# cyboard.net
KiCad netlist of a schematic drawn in EAGLE
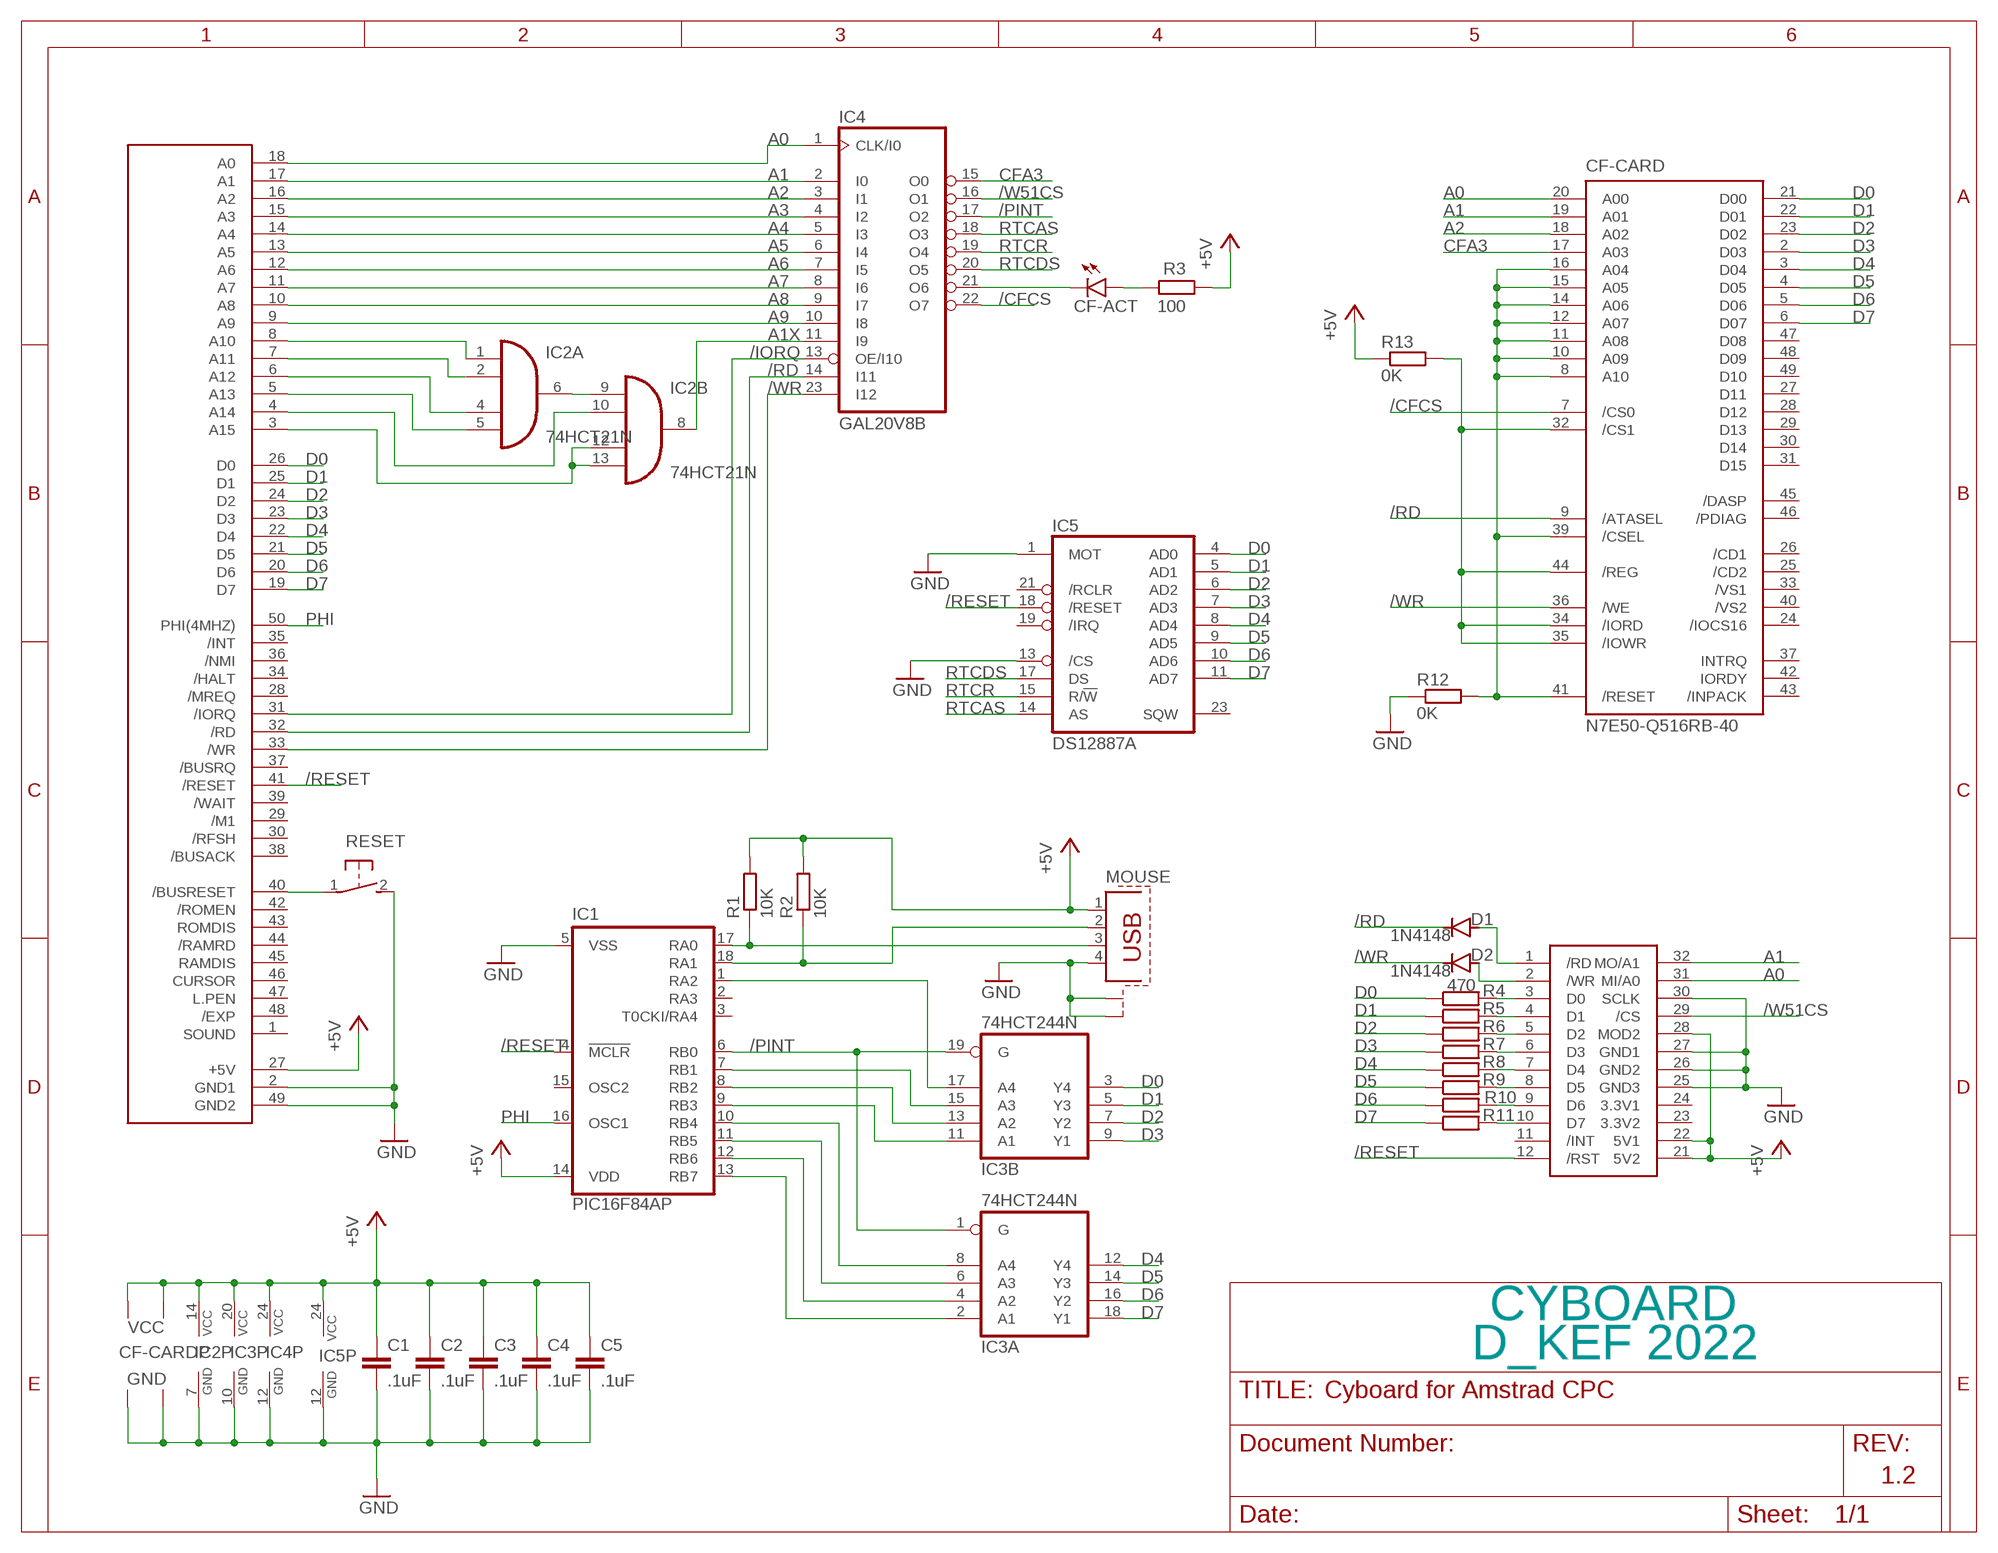
[diagram p0: schematic, sheet 1]

(export (version "E")
  (design (tool "Eeschema 10.0.6"))
  (components
    (comp (ref "C1")
      (value ".1uF")
      (footprint "eagle-import:C025-025X050")
      (libsource (lib "eagle-import") (part "C-EU025-025X050"))
    )
    (comp (ref "C2")
      (value ".1uF")
      (footprint "eagle-import:C025-025X050")
      (libsource (lib "eagle-import") (part "C-EU025-025X050"))
    )
    (comp (ref "C3")
      (value ".1uF")
      (footprint "eagle-import:C025-025X050")
      (libsource (lib "eagle-import") (part "C-EU025-025X050"))
    )
    (comp (ref "C4")
      (value ".1uF")
      (footprint "eagle-import:C025-025X050")
      (libsource (lib "eagle-import") (part "C-EU025-025X050"))
    )
    (comp (ref "C5")
      (value ".1uF")
      (footprint "eagle-import:C025-025X050")
      (libsource (lib "eagle-import") (part "C-EU025-025X050"))
    )
    (comp (ref "CF-ACT")
      (value "CF ACT")
      (footprint "eagle-import:LED3MM")
      (libsource (lib "eagle-import") (part "LED3MM"))
    )
    (comp (ref "CF-CARD")
      (value "N7E50-Q516RB-40")
      (footprint "eagle-import:3M-N7E50")
      (libsource (lib "eagle-import") (part "CF-CARD-HEADERHYBRID-1"))
    )
    (comp (ref "CON1")
      (value "CPCBUS")
      (footprint "eagle-import:2X25")
      (libsource (lib "eagle-import") (part "AMSTRAD_CPC_BUSP"))
    )
    (comp (ref "D1")
      (value "1N4148")
      (footprint "eagle-import:DO35-7")
      (libsource (lib "eagle-import") (part "1N4148DO35-7"))
    )
    (comp (ref "D2")
      (value "1N4148")
      (footprint "eagle-import:DO35-7")
      (libsource (lib "eagle-import") (part "1N4148DO35-7"))
    )
    (comp (ref "IC1")
      (value "PIC16F84AP")
      (footprint "eagle-import:DIL18")
      (fields (field (name "MF") "MICROCHIP") (field (name "MPN") "PIC16F84A-04I/P"))
      (libsource (lib "eagle-import") (part "PIC16F8P4A"))
    )
    (comp (ref "IC2")
      (value "74HCT21N")
      (footprint "eagle-import:DIL14")
      (libsource (lib "eagle-import") (part "7421NHC"))
    )
    (comp (ref "IC3")
      (value "74HCT244N")
      (footprint "eagle-import:DIL20")
      (libsource (lib "eagle-import") (part "74244NHCT"))
    )
    (comp (ref "IC4")
      (value "GAL20V8B")
      (footprint "eagle-import:DIL24-3")
      (fields (field (name "MF") "FARNELL") (field (name "MPN") "GAL20V8B-25QP"))
      (libsource (lib "eagle-import") (part "20V8"))
    )
    (comp (ref "IC5")
      (value "DS12887A")
      (footprint "eagle-import:DIL24")
      (libsource (lib "eagle-import") (part "DS12887"))
    )
    (comp (ref "MOUSE")
      (value "PN87520-S")
      (footprint "eagle-import:PN87520-S")
      (libsource (lib "eagle-import") (part "PN87520-S"))
    )
    (comp (ref "R1")
      (value "10K")
      (footprint "eagle-import:0204_7")
      (libsource (lib "eagle-import") (part "R-EU_0204/7"))
    )
    (comp (ref "R2")
      (value "10K")
      (footprint "eagle-import:0204_7")
      (libsource (lib "eagle-import") (part "R-EU_0204/7"))
    )
    (comp (ref "R3")
      (value "100")
      (footprint "eagle-import:0204_7")
      (libsource (lib "eagle-import") (part "R-EU_0204/7"))
    )
    (comp (ref "R4")
      (value "470")
      (footprint "eagle-import:0204_7")
      (libsource (lib "eagle-import") (part "R-EU_0204/7"))
    )
    (comp (ref "R5")
      (value "470")
      (footprint "eagle-import:0204_7")
      (libsource (lib "eagle-import") (part "R-EU_0204/7"))
    )
    (comp (ref "R6")
      (value "470")
      (footprint "eagle-import:0204_7")
      (libsource (lib "eagle-import") (part "R-EU_0204/7"))
    )
    (comp (ref "R7")
      (value "470")
      (footprint "eagle-import:0204_7")
      (libsource (lib "eagle-import") (part "R-EU_0204/7"))
    )
    (comp (ref "R8")
      (value "470")
      (footprint "eagle-import:0204_7")
      (libsource (lib "eagle-import") (part "R-EU_0204/7"))
    )
    (comp (ref "R9")
      (value "470")
      (footprint "eagle-import:0204_7")
      (libsource (lib "eagle-import") (part "R-EU_0204/7"))
    )
    (comp (ref "R10")
      (value "470")
      (footprint "eagle-import:0204_7")
      (libsource (lib "eagle-import") (part "R-EU_0204/7"))
    )
    (comp (ref "R11")
      (value "470")
      (footprint "eagle-import:0204_7")
      (libsource (lib "eagle-import") (part "R-EU_0204/7"))
    )
    (comp (ref "R12")
      (value "0K")
      (footprint "eagle-import:0204_7")
      (libsource (lib "eagle-import") (part "R-EU_0204/7"))
    )
    (comp (ref "R13")
      (value "0K")
      (footprint "eagle-import:0204_7")
      (libsource (lib "eagle-import") (part "R-EU_0204/7"))
    )
    (comp (ref "RESET")
      (value "Reset")
      (footprint "eagle-import:B3F-31XX")
      (fields (field (name "MPN") "B3F-3100"))
      (libsource (lib "eagle-import") (part "31-XX"))
    )
    (comp (ref "W5100S-MODULE")
      (value "W5100S-NETWORK-MODULE")
      (footprint "eagle-import:W5100S-NETWORK-MODULE")
      (libsource (lib "eagle-import") (part "W5100S-NETWORK-MODULE"))
    )
  )
  (nets
    (net (code "1") (name "+5V") (class "Default")
      (node (ref "C1") (pin "1") (pinfunction "1_1") (pintype "passive"))
      (node (ref "C2") (pin "1") (pinfunction "1_1") (pintype "passive"))
      (node (ref "C3") (pin "1") (pinfunction "1_1") (pintype "passive"))
      (node (ref "C4") (pin "1") (pinfunction "1_1") (pintype "passive"))
      (node (ref "C5") (pin "1") (pinfunction "1_1") (pintype "passive"))
      (node (ref "CF-CARD") (pin "13") (pinfunction "VCC2_13") (pintype "power_in"))
      (node (ref "CF-CARD") (pin "38") (pinfunction "VCC1_38") (pintype "power_in"))
      (node (ref "CON1") (pin "27") (pinfunction "+5V_27") (pintype "bidirectional"))
      (node (ref "IC1") (pin "14") (pinfunction "VDD_14") (pintype "power_in"))
      (node (ref "IC2") (pin "14") (pinfunction "VCC_14") (pintype "power_in"))
      (node (ref "IC3") (pin "20") (pinfunction "VCC_20") (pintype "power_in"))
      (node (ref "IC4") (pin "24") (pinfunction "VCC_24") (pintype "power_in"))
      (node (ref "IC5") (pin "24") (pinfunction "VCC_24") (pintype "power_in"))
      (node (ref "MOUSE") (pin "1") (pinfunction "1_1") (pintype "passive"))
      (node (ref "R1") (pin "2") (pinfunction "2_2") (pintype "passive"))
      (node (ref "R13") (pin "1") (pinfunction "1_1") (pintype "passive"))
      (node (ref "R2") (pin "2") (pinfunction "2_2") (pintype "passive"))
      (node (ref "R3") (pin "1") (pinfunction "1_1") (pintype "passive"))
      (node (ref "W5100S-MODULE") (pin "21") (pinfunction "5V2_21") (pintype "power_in"))
      (node (ref "W5100S-MODULE") (pin "22") (pinfunction "5V1_22") (pintype "power_in"))
      (node (ref "W5100S-MODULE") (pin "28") (pinfunction "MOD2_28") (pintype "passive"))
    )
    (net (code "2") (name "/3.3V1") (class "Default")
      (node (ref "W5100S-MODULE") (pin "24") (pinfunction "3.3V1_24") (pintype "power_in"))
    )
    (net (code "3") (name "/3.3V2") (class "Default")
      (node (ref "W5100S-MODULE") (pin "23") (pinfunction "3.3V2_23") (pintype "power_in"))
    )
    (net (code "4") (name "/A0") (class "Default")
      (node (ref "CF-CARD") (pin "20") (pinfunction "A00_20") (pintype "input"))
      (node (ref "CON1") (pin "18") (pinfunction "A0_18") (pintype "bidirectional"))
      (node (ref "IC4") (pin "1") (pinfunction "CLK/I0_1") (pintype "input"))
      (node (ref "W5100S-MODULE") (pin "31") (pinfunction "MI/A0_31") (pintype "input"))
    )
    (net (code "5") (name "/A1") (class "Default")
      (node (ref "CF-CARD") (pin "19") (pinfunction "A01_19") (pintype "input"))
      (node (ref "CON1") (pin "17") (pinfunction "A1_17") (pintype "bidirectional"))
      (node (ref "IC4") (pin "2") (pinfunction "I0_2") (pintype "input"))
      (node (ref "W5100S-MODULE") (pin "32") (pinfunction "MO/A1_32") (pintype "bidirectional"))
    )
    (net (code "6") (name "/A1X") (class "Default")
      (node (ref "IC2") (pin "8") (pinfunction "O_8") (pintype "output"))
      (node (ref "IC4") (pin "11") (pinfunction "I9_11") (pintype "input"))
    )
    (net (code "7") (name "/A2") (class "Default")
      (node (ref "CF-CARD") (pin "18") (pinfunction "A02_18") (pintype "input"))
      (node (ref "CON1") (pin "16") (pinfunction "A2_16") (pintype "bidirectional"))
      (node (ref "IC4") (pin "3") (pinfunction "I1_3") (pintype "input"))
    )
    (net (code "8") (name "/A3") (class "Default")
      (node (ref "CON1") (pin "15") (pinfunction "A3_15") (pintype "bidirectional"))
      (node (ref "IC4") (pin "4") (pinfunction "I2_4") (pintype "input"))
    )
    (net (code "9") (name "/A4") (class "Default")
      (node (ref "CON1") (pin "14") (pinfunction "A4_14") (pintype "bidirectional"))
      (node (ref "IC4") (pin "5") (pinfunction "I3_5") (pintype "input"))
    )
    (net (code "10") (name "/A5") (class "Default")
      (node (ref "CON1") (pin "13") (pinfunction "A5_13") (pintype "bidirectional"))
      (node (ref "IC4") (pin "6") (pinfunction "I4_6") (pintype "input"))
    )
    (net (code "11") (name "/A6") (class "Default")
      (node (ref "CON1") (pin "12") (pinfunction "A6_12") (pintype "bidirectional"))
      (node (ref "IC4") (pin "7") (pinfunction "I5_7") (pintype "input"))
    )
    (net (code "12") (name "/A7") (class "Default")
      (node (ref "CON1") (pin "11") (pinfunction "A7_11") (pintype "bidirectional"))
      (node (ref "IC4") (pin "8") (pinfunction "I6_8") (pintype "input"))
    )
    (net (code "13") (name "/A8") (class "Default")
      (node (ref "CON1") (pin "10") (pinfunction "A8_10") (pintype "bidirectional"))
      (node (ref "IC4") (pin "9") (pinfunction "I7_9") (pintype "input"))
    )
    (net (code "14") (name "/A9") (class "Default")
      (node (ref "CON1") (pin "9") (pinfunction "A9_9") (pintype "bidirectional"))
      (node (ref "IC4") (pin "10") (pinfunction "I8_10") (pintype "input"))
    )
    (net (code "15") (name "/CFA3") (class "Default")
      (node (ref "CF-CARD") (pin "17") (pinfunction "A03_17") (pintype "input"))
      (node (ref "IC4") (pin "15") (pinfunction "O0_15") (pintype "bidirectional"))
    )
    (net (code "16") (name "/D0") (class "Default")
      (node (ref "CF-CARD") (pin "21") (pinfunction "D00_21") (pintype "bidirectional"))
      (node (ref "CON1") (pin "26") (pinfunction "D0_26") (pintype "bidirectional"))
      (node (ref "IC3") (pin "3") (pinfunction "Y4_3") (pintype "tri_state"))
      (node (ref "IC5") (pin "4") (pinfunction "AD0_4") (pintype "bidirectional"))
      (node (ref "R4") (pin "1") (pinfunction "1_1") (pintype "passive"))
    )
    (net (code "17") (name "/D1") (class "Default")
      (node (ref "CF-CARD") (pin "22") (pinfunction "D01_22") (pintype "bidirectional"))
      (node (ref "CON1") (pin "25") (pinfunction "D1_25") (pintype "bidirectional"))
      (node (ref "IC3") (pin "5") (pinfunction "Y3_5") (pintype "tri_state"))
      (node (ref "IC5") (pin "5") (pinfunction "AD1_5") (pintype "bidirectional"))
      (node (ref "R5") (pin "1") (pinfunction "1_1") (pintype "passive"))
    )
    (net (code "18") (name "/D2") (class "Default")
      (node (ref "CF-CARD") (pin "23") (pinfunction "D02_23") (pintype "bidirectional"))
      (node (ref "CON1") (pin "24") (pinfunction "D2_24") (pintype "bidirectional"))
      (node (ref "IC3") (pin "7") (pinfunction "Y2_7") (pintype "tri_state"))
      (node (ref "IC5") (pin "6") (pinfunction "AD2_6") (pintype "bidirectional"))
      (node (ref "R6") (pin "1") (pinfunction "1_1") (pintype "passive"))
    )
    (net (code "19") (name "/D3") (class "Default")
      (node (ref "CF-CARD") (pin "2") (pinfunction "D03_2") (pintype "bidirectional"))
      (node (ref "CON1") (pin "23") (pinfunction "D3_23") (pintype "bidirectional"))
      (node (ref "IC3") (pin "9") (pinfunction "Y1_9") (pintype "tri_state"))
      (node (ref "IC5") (pin "7") (pinfunction "AD3_7") (pintype "bidirectional"))
      (node (ref "R7") (pin "1") (pinfunction "1_1") (pintype "passive"))
    )
    (net (code "20") (name "/D4") (class "Default")
      (node (ref "CF-CARD") (pin "3") (pinfunction "D04_3") (pintype "bidirectional"))
      (node (ref "CON1") (pin "22") (pinfunction "D4_22") (pintype "bidirectional"))
      (node (ref "IC3") (pin "12") (pinfunction "Y4_12") (pintype "tri_state"))
      (node (ref "IC5") (pin "8") (pinfunction "AD4_8") (pintype "bidirectional"))
      (node (ref "R8") (pin "1") (pinfunction "1_1") (pintype "passive"))
    )
    (net (code "21") (name "/D5") (class "Default")
      (node (ref "CF-CARD") (pin "4") (pinfunction "D05_4") (pintype "bidirectional"))
      (node (ref "CON1") (pin "21") (pinfunction "D5_21") (pintype "bidirectional"))
      (node (ref "IC3") (pin "14") (pinfunction "Y3_14") (pintype "tri_state"))
      (node (ref "IC5") (pin "9") (pinfunction "AD5_9") (pintype "bidirectional"))
      (node (ref "R9") (pin "1") (pinfunction "1_1") (pintype "passive"))
    )
    (net (code "22") (name "/D6") (class "Default")
      (node (ref "CF-CARD") (pin "5") (pinfunction "D06_5") (pintype "bidirectional"))
      (node (ref "CON1") (pin "20") (pinfunction "D6_20") (pintype "bidirectional"))
      (node (ref "IC3") (pin "16") (pinfunction "Y2_16") (pintype "tri_state"))
      (node (ref "IC5") (pin "10") (pinfunction "AD6_10") (pintype "bidirectional"))
      (node (ref "R10") (pin "1") (pinfunction "1_1") (pintype "passive"))
    )
    (net (code "23") (name "/D7") (class "Default")
      (node (ref "CF-CARD") (pin "6") (pinfunction "D07_6") (pintype "bidirectional"))
      (node (ref "CON1") (pin "19") (pinfunction "D7_19") (pintype "bidirectional"))
      (node (ref "IC3") (pin "18") (pinfunction "Y1_18") (pintype "tri_state"))
      (node (ref "IC5") (pin "11") (pinfunction "AD7_11") (pintype "bidirectional"))
      (node (ref "R11") (pin "1") (pinfunction "1_1") (pintype "passive"))
    )
    (net (code "24") (name "/PHI") (class "Default")
      (node (ref "CON1") (pin "50") (pinfunction "PHI(4MHZ)_50") (pintype "bidirectional"))
      (node (ref "IC1") (pin "16") (pinfunction "OSC1_16") (pintype "input"))
    )
    (net (code "25") (name "/RTCAS") (class "Default")
      (node (ref "IC4") (pin "18") (pinfunction "O3_18") (pintype "bidirectional"))
      (node (ref "IC5") (pin "14") (pinfunction "AS_14") (pintype "input"))
    )
    (net (code "26") (name "/RTCDS") (class "Default")
      (node (ref "IC4") (pin "20") (pinfunction "O5_20") (pintype "bidirectional"))
      (node (ref "IC5") (pin "17") (pinfunction "DS_17") (pintype "input"))
    )
    (net (code "27") (name "/RTCR") (class "Default")
      (node (ref "IC4") (pin "19") (pinfunction "O4_19") (pintype "bidirectional"))
      (node (ref "IC5") (pin "15") (pinfunction "R/~{W}_15") (pintype "input"))
    )
    (net (code "28") (name "/{slash}CFCS") (class "Default")
      (node (ref "CF-CARD") (pin "7") (pinfunction "/CS0_7") (pintype "input"))
      (node (ref "IC4") (pin "22") (pinfunction "O7_22") (pintype "bidirectional"))
    )
    (net (code "29") (name "/{slash}IORQ") (class "Default")
      (node (ref "CON1") (pin "31") (pinfunction "/IORQ_31") (pintype "bidirectional"))
      (node (ref "IC4") (pin "13") (pinfunction "OE/I10_13") (pintype "input"))
    )
    (net (code "30") (name "/{slash}PINT") (class "Default")
      (node (ref "IC1") (pin "6") (pinfunction "RB0_6") (pintype "bidirectional"))
      (node (ref "IC3") (pin "1") (pinfunction "G_1") (pintype "input"))
      (node (ref "IC3") (pin "19") (pinfunction "G_19") (pintype "input"))
      (node (ref "IC4") (pin "17") (pinfunction "O2_17") (pintype "bidirectional"))
    )
    (net (code "31") (name "/{slash}RD") (class "Default")
      (node (ref "CF-CARD") (pin "9") (pinfunction "/ATASEL_9") (pintype "input"))
      (node (ref "CON1") (pin "32") (pinfunction "/RD_32") (pintype "bidirectional"))
      (node (ref "D1") (pin "C") (pinfunction "C_C") (pintype "passive"))
      (node (ref "IC4") (pin "14") (pinfunction "I11_14") (pintype "input"))
    )
    (net (code "32") (name "/{slash}RESET") (class "Default")
      (node (ref "CON1") (pin "41") (pinfunction "/RESET_41") (pintype "bidirectional"))
      (node (ref "IC1") (pin "4") (pinfunction "~{MCLR}_4") (pintype "input"))
      (node (ref "IC5") (pin "18") (pinfunction "/RESET_18") (pintype "input"))
      (node (ref "W5100S-MODULE") (pin "12") (pinfunction "/RST_12") (pintype "input"))
    )
    (net (code "33") (name "/{slash}W51CS") (class "Default")
      (node (ref "IC4") (pin "16") (pinfunction "O1_16") (pintype "bidirectional"))
      (node (ref "W5100S-MODULE") (pin "29") (pinfunction "/CS_29") (pintype "input"))
    )
    (net (code "34") (name "/{slash}WR") (class "Default")
      (node (ref "CF-CARD") (pin "36") (pinfunction "/WE_36") (pintype "input"))
      (node (ref "CON1") (pin "33") (pinfunction "/WR_33") (pintype "bidirectional"))
      (node (ref "D2") (pin "C") (pinfunction "C_C") (pintype "passive"))
      (node (ref "IC4") (pin "23") (pinfunction "I12_23") (pintype "input"))
    )
    (net (code "35") (name "GND") (class "Default")
      (node (ref "C1") (pin "2") (pinfunction "2_2") (pintype "passive"))
      (node (ref "C2") (pin "2") (pinfunction "2_2") (pintype "passive"))
      (node (ref "C3") (pin "2") (pinfunction "2_2") (pintype "passive"))
      (node (ref "C4") (pin "2") (pinfunction "2_2") (pintype "passive"))
      (node (ref "C5") (pin "2") (pinfunction "2_2") (pintype "passive"))
      (node (ref "CF-CARD") (pin "1") (pinfunction "GND1_1") (pintype "power_in"))
      (node (ref "CF-CARD") (pin "50") (pinfunction "GND2_50") (pintype "power_in"))
      (node (ref "CON1") (pin "2") (pinfunction "GND1_2") (pintype "bidirectional"))
      (node (ref "CON1") (pin "49") (pinfunction "GND2_49") (pintype "bidirectional"))
      (node (ref "IC1") (pin "5") (pinfunction "VSS_5") (pintype "power_in"))
      (node (ref "IC2") (pin "7") (pinfunction "GND_7") (pintype "power_in"))
      (node (ref "IC3") (pin "10") (pinfunction "GND_10") (pintype "power_in"))
      (node (ref "IC4") (pin "12") (pinfunction "GND_12") (pintype "power_in"))
      (node (ref "IC5") (pin "1") (pinfunction "MOT_1") (pintype "input"))
      (node (ref "IC5") (pin "12") (pinfunction "GND_12") (pintype "power_in"))
      (node (ref "IC5") (pin "13") (pinfunction "/CS_13") (pintype "input"))
      (node (ref "MOUSE") (pin "4") (pinfunction "4_4") (pintype "passive"))
      (node (ref "MOUSE") (pin "S1") (pinfunction "S1_S1") (pintype "passive"))
      (node (ref "MOUSE") (pin "S2") (pinfunction "S2_S2") (pintype "passive"))
      (node (ref "R12") (pin "1") (pinfunction "1_1") (pintype "passive"))
      (node (ref "RESET") (pin "2") (pinfunction "S_2") (pintype "passive"))
      (node (ref "W5100S-MODULE") (pin "25") (pinfunction "GND3_25") (pintype "power_in"))
      (node (ref "W5100S-MODULE") (pin "26") (pinfunction "GND2_26") (pintype "power_in"))
      (node (ref "W5100S-MODULE") (pin "27") (pinfunction "GND1_27") (pintype "power_in"))
      (node (ref "W5100S-MODULE") (pin "30") (pinfunction "SCLK_30") (pintype "output"))
    )
    (net (code "36") (name "Net-(CF-ACT-C)") (class "Default")
      (node (ref "CF-ACT") (pin "K") (pinfunction "C_K") (pintype "passive"))
      (node (ref "IC4") (pin "21") (pinfunction "O6_21") (pintype "bidirectional"))
    )
    (net (code "37") (name "Net-(CF-ACT-PadA)") (class "Default")
      (node (ref "CF-ACT") (pin "A") (pinfunction "A_A") (pintype "passive"))
      (node (ref "R3") (pin "2") (pinfunction "2_2") (pintype "passive"))
    )
    (net (code "38") (name "Net-(CF-CARDA-A04)") (class "Default")
      (node (ref "CF-CARD") (pin "10") (pinfunction "A09_10") (pintype "input"))
      (node (ref "CF-CARD") (pin "11") (pinfunction "A08_11") (pintype "input"))
      (node (ref "CF-CARD") (pin "12") (pinfunction "A07_12") (pintype "input"))
      (node (ref "CF-CARD") (pin "14") (pinfunction "A06_14") (pintype "input"))
      (node (ref "CF-CARD") (pin "15") (pinfunction "A05_15") (pintype "input"))
      (node (ref "CF-CARD") (pin "16") (pinfunction "A04_16") (pintype "input"))
      (node (ref "CF-CARD") (pin "39") (pinfunction "/CSEL_39") (pintype "input"))
      (node (ref "CF-CARD") (pin "41") (pinfunction "/RESET_41") (pintype "input"))
      (node (ref "CF-CARD") (pin "8") (pinfunction "A10_8") (pintype "input"))
      (node (ref "R12") (pin "2") (pinfunction "2_2") (pintype "passive"))
    )
    (net (code "39") (name "Net-(CF-CARDA-{slash}CS1)") (class "Default")
      (node (ref "CF-CARD") (pin "32") (pinfunction "/CS1_32") (pintype "input"))
      (node (ref "CF-CARD") (pin "34") (pinfunction "/IORD_34") (pintype "input"))
      (node (ref "CF-CARD") (pin "35") (pinfunction "/IOWR_35") (pintype "input"))
      (node (ref "CF-CARD") (pin "44") (pinfunction "/REG_44") (pintype "input"))
      (node (ref "R13") (pin "2") (pinfunction "2_2") (pintype "passive"))
    )
    (net (code "40") (name "Net-(CON1-A10)") (class "Default")
      (node (ref "CON1") (pin "8") (pinfunction "A10_8") (pintype "bidirectional"))
      (node (ref "IC2") (pin "1") (pinfunction "I0_1") (pintype "input"))
    )
    (net (code "41") (name "Net-(CON1-A11)") (class "Default")
      (node (ref "CON1") (pin "7") (pinfunction "A11_7") (pintype "bidirectional"))
      (node (ref "IC2") (pin "2") (pinfunction "I1_2") (pintype "input"))
    )
    (net (code "42") (name "Net-(CON1-A12)") (class "Default")
      (node (ref "CON1") (pin "6") (pinfunction "A12_6") (pintype "bidirectional"))
      (node (ref "IC2") (pin "4") (pinfunction "I2_4") (pintype "input"))
    )
    (net (code "43") (name "Net-(CON1-A13)") (class "Default")
      (node (ref "CON1") (pin "5") (pinfunction "A13_5") (pintype "bidirectional"))
      (node (ref "IC2") (pin "5") (pinfunction "I3_5") (pintype "input"))
    )
    (net (code "44") (name "Net-(CON1-A14)") (class "Default")
      (node (ref "CON1") (pin "4") (pinfunction "A14_4") (pintype "bidirectional"))
      (node (ref "IC2") (pin "10") (pinfunction "I1_10") (pintype "input"))
    )
    (net (code "45") (name "Net-(CON1-A15)") (class "Default")
      (node (ref "CON1") (pin "3") (pinfunction "A15_3") (pintype "bidirectional"))
      (node (ref "IC2") (pin "12") (pinfunction "I2_12") (pintype "input"))
      (node (ref "IC2") (pin "13") (pinfunction "I3_13") (pintype "input"))
    )
    (net (code "46") (name "Net-(CON1-{slash}BUSRESET)") (class "Default")
      (node (ref "CON1") (pin "40") (pinfunction "/BUSRESET_40") (pintype "bidirectional"))
      (node (ref "RESET") (pin "1") (pinfunction "P_1") (pintype "passive"))
    )
    (net (code "47") (name "Net-(IC1-RA0)") (class "Default")
      (node (ref "IC1") (pin "17") (pinfunction "RA0_17") (pintype "bidirectional"))
      (node (ref "MOUSE") (pin "3") (pinfunction "3_3") (pintype "passive"))
      (node (ref "R1") (pin "1") (pinfunction "1_1") (pintype "passive"))
    )
    (net (code "48") (name "Net-(IC1-RA1)") (class "Default")
      (node (ref "IC1") (pin "18") (pinfunction "RA1_18") (pintype "bidirectional"))
      (node (ref "MOUSE") (pin "2") (pinfunction "2_2") (pintype "passive"))
      (node (ref "R2") (pin "1") (pinfunction "1_1") (pintype "passive"))
    )
    (net (code "49") (name "Net-(IC1-RA2)") (class "Default")
      (node (ref "IC1") (pin "1") (pinfunction "RA2_1") (pintype "bidirectional"))
      (node (ref "IC3") (pin "17") (pinfunction "A4_17") (pintype "input"))
    )
    (net (code "50") (name "Net-(IC1-RB1)") (class "Default")
      (node (ref "IC1") (pin "7") (pinfunction "RB1_7") (pintype "bidirectional"))
      (node (ref "IC3") (pin "15") (pinfunction "A3_15") (pintype "input"))
    )
    (net (code "51") (name "Net-(IC1-RB2)") (class "Default")
      (node (ref "IC1") (pin "8") (pinfunction "RB2_8") (pintype "bidirectional"))
      (node (ref "IC3") (pin "13") (pinfunction "A2_13") (pintype "input"))
    )
    (net (code "52") (name "Net-(IC1-RB3)") (class "Default")
      (node (ref "IC1") (pin "9") (pinfunction "RB3_9") (pintype "bidirectional"))
      (node (ref "IC3") (pin "11") (pinfunction "A1_11") (pintype "input"))
    )
    (net (code "53") (name "Net-(IC1-RB4)") (class "Default")
      (node (ref "IC1") (pin "10") (pinfunction "RB4_10") (pintype "bidirectional"))
      (node (ref "IC3") (pin "8") (pinfunction "A4_8") (pintype "input"))
    )
    (net (code "54") (name "Net-(IC1-RB5)") (class "Default")
      (node (ref "IC1") (pin "11") (pinfunction "RB5_11") (pintype "bidirectional"))
      (node (ref "IC3") (pin "6") (pinfunction "A3_6") (pintype "input"))
    )
    (net (code "55") (name "Net-(IC1-RB6)") (class "Default")
      (node (ref "IC1") (pin "12") (pinfunction "RB6_12") (pintype "bidirectional"))
      (node (ref "IC3") (pin "4") (pinfunction "A2_4") (pintype "input"))
    )
    (net (code "56") (name "Net-(IC1-RB7)") (class "Default")
      (node (ref "IC1") (pin "13") (pinfunction "RB7_13") (pintype "bidirectional"))
      (node (ref "IC3") (pin "2") (pinfunction "A1_2") (pintype "input"))
    )
    (net (code "57") (name "Net-(IC2A-O)") (class "Default")
      (node (ref "IC2") (pin "6") (pinfunction "O_6") (pintype "output"))
      (node (ref "IC2") (pin "9") (pinfunction "I0_9") (pintype "input"))
    )
    (net (code "58") (name "Net-(W5100S-MODULE-D0)") (class "Default")
      (node (ref "R4") (pin "2") (pinfunction "2_2") (pintype "passive"))
      (node (ref "W5100S-MODULE") (pin "3") (pinfunction "D0_3") (pintype "bidirectional"))
    )
    (net (code "59") (name "Net-(W5100S-MODULE-D1)") (class "Default")
      (node (ref "R5") (pin "2") (pinfunction "2_2") (pintype "passive"))
      (node (ref "W5100S-MODULE") (pin "4") (pinfunction "D1_4") (pintype "bidirectional"))
    )
    (net (code "60") (name "Net-(W5100S-MODULE-D2)") (class "Default")
      (node (ref "R6") (pin "2") (pinfunction "2_2") (pintype "passive"))
      (node (ref "W5100S-MODULE") (pin "5") (pinfunction "D2_5") (pintype "bidirectional"))
    )
    (net (code "61") (name "Net-(W5100S-MODULE-D3)") (class "Default")
      (node (ref "R7") (pin "2") (pinfunction "2_2") (pintype "passive"))
      (node (ref "W5100S-MODULE") (pin "6") (pinfunction "D3_6") (pintype "bidirectional"))
    )
    (net (code "62") (name "Net-(W5100S-MODULE-D4)") (class "Default")
      (node (ref "R8") (pin "2") (pinfunction "2_2") (pintype "passive"))
      (node (ref "W5100S-MODULE") (pin "7") (pinfunction "D4_7") (pintype "bidirectional"))
    )
    (net (code "63") (name "Net-(W5100S-MODULE-D5)") (class "Default")
      (node (ref "R9") (pin "2") (pinfunction "2_2") (pintype "passive"))
      (node (ref "W5100S-MODULE") (pin "8") (pinfunction "D5_8") (pintype "bidirectional"))
    )
    (net (code "64") (name "Net-(W5100S-MODULE-D6)") (class "Default")
      (node (ref "R10") (pin "2") (pinfunction "2_2") (pintype "passive"))
      (node (ref "W5100S-MODULE") (pin "9") (pinfunction "D6_9") (pintype "bidirectional"))
    )
    (net (code "65") (name "Net-(W5100S-MODULE-D7)") (class "Default")
      (node (ref "R11") (pin "2") (pinfunction "2_2") (pintype "passive"))
      (node (ref "W5100S-MODULE") (pin "10") (pinfunction "D7_10") (pintype "bidirectional"))
    )
    (net (code "66") (name "Net-(W5100S-MODULE-{slash}RD)") (class "Default")
      (node (ref "D1") (pin "A") (pinfunction "A_A") (pintype "passive"))
      (node (ref "W5100S-MODULE") (pin "1") (pinfunction "/RD_1") (pintype "input"))
    )
    (net (code "67") (name "Net-(W5100S-MODULE-{slash}WR)") (class "Default")
      (node (ref "D2") (pin "A") (pinfunction "A_A") (pintype "passive"))
      (node (ref "W5100S-MODULE") (pin "2") (pinfunction "/WR_2") (pintype "input"))
    )
    (net (code "68") (name "unconnected-(CF-CARDA-D08-Pad47)") (class "Default")
      (node (ref "CF-CARD") (pin "47") (pinfunction "D08_47") (pintype "bidirectional"))
    )
    (net (code "69") (name "unconnected-(CF-CARDA-D09-Pad48)") (class "Default")
      (node (ref "CF-CARD") (pin "48") (pinfunction "D09_48") (pintype "bidirectional"))
    )
    (net (code "70") (name "unconnected-(CF-CARDA-D10-Pad49)") (class "Default")
      (node (ref "CF-CARD") (pin "49") (pinfunction "D10_49") (pintype "bidirectional"))
    )
    (net (code "71") (name "unconnected-(CF-CARDA-D11-Pad27)") (class "Default")
      (node (ref "CF-CARD") (pin "27") (pinfunction "D11_27") (pintype "bidirectional"))
    )
    (net (code "72") (name "unconnected-(CF-CARDA-D12-Pad28)") (class "Default")
      (node (ref "CF-CARD") (pin "28") (pinfunction "D12_28") (pintype "bidirectional"))
    )
    (net (code "73") (name "unconnected-(CF-CARDA-D13-Pad29)") (class "Default")
      (node (ref "CF-CARD") (pin "29") (pinfunction "D13_29") (pintype "bidirectional"))
    )
    (net (code "74") (name "unconnected-(CF-CARDA-D14-Pad30)") (class "Default")
      (node (ref "CF-CARD") (pin "30") (pinfunction "D14_30") (pintype "bidirectional"))
    )
    (net (code "75") (name "unconnected-(CF-CARDA-D15-Pad31)") (class "Default")
      (node (ref "CF-CARD") (pin "31") (pinfunction "D15_31") (pintype "bidirectional"))
    )
    (net (code "76") (name "unconnected-(CF-CARDA-INTRQ-Pad37)") (class "Default")
      (node (ref "CF-CARD") (pin "37") (pinfunction "INTRQ_37") (pintype "output"))
    )
    (net (code "77") (name "unconnected-(CF-CARDA-IORDY-Pad42)") (class "Default")
      (node (ref "CF-CARD") (pin "42") (pinfunction "IORDY_42") (pintype "output"))
    )
    (net (code "78") (name "unconnected-(CF-CARDA-{slash}CD1-Pad26)") (class "Default")
      (node (ref "CF-CARD") (pin "26") (pinfunction "/CD1_26") (pintype "output"))
    )
    (net (code "79") (name "unconnected-(CF-CARDA-{slash}CD2-Pad25)") (class "Default")
      (node (ref "CF-CARD") (pin "25") (pinfunction "/CD2_25") (pintype "output"))
    )
    (net (code "80") (name "unconnected-(CF-CARDA-{slash}DASP-Pad45)") (class "Default")
      (node (ref "CF-CARD") (pin "45") (pinfunction "/DASP_45") (pintype "bidirectional"))
    )
    (net (code "81") (name "unconnected-(CF-CARDA-{slash}INPACK-Pad43)") (class "Default")
      (node (ref "CF-CARD") (pin "43") (pinfunction "/INPACK_43") (pintype "output"))
    )
    (net (code "82") (name "unconnected-(CF-CARDA-{slash}IOCS16-Pad24)") (class "Default")
      (node (ref "CF-CARD") (pin "24") (pinfunction "/IOCS16_24") (pintype "output"))
    )
    (net (code "83") (name "unconnected-(CF-CARDA-{slash}PDIAG-Pad46)") (class "Default")
      (node (ref "CF-CARD") (pin "46") (pinfunction "/PDIAG_46") (pintype "bidirectional"))
    )
    (net (code "84") (name "unconnected-(CF-CARDA-{slash}VS1-Pad33)") (class "Default")
      (node (ref "CF-CARD") (pin "33") (pinfunction "/VS1_33") (pintype "output"))
    )
    (net (code "85") (name "unconnected-(CF-CARDA-{slash}VS2-Pad40)") (class "Default")
      (node (ref "CF-CARD") (pin "40") (pinfunction "/VS2_40") (pintype "output"))
    )
    (net (code "86") (name "unconnected-(CON1-CURSOR-Pad46)") (class "Default")
      (node (ref "CON1") (pin "46") (pinfunction "CURSOR_46") (pintype "bidirectional"))
    )
    (net (code "87") (name "unconnected-(CON1-L.PEN-Pad47)") (class "Default")
      (node (ref "CON1") (pin "47") (pinfunction "L.PEN_47") (pintype "bidirectional"))
    )
    (net (code "88") (name "unconnected-(CON1-RAMDIS-Pad45)") (class "Default")
      (node (ref "CON1") (pin "45") (pinfunction "RAMDIS_45") (pintype "bidirectional"))
    )
    (net (code "89") (name "unconnected-(CON1-ROMDIS-Pad43)") (class "Default")
      (node (ref "CON1") (pin "43") (pinfunction "ROMDIS_43") (pintype "bidirectional"))
    )
    (net (code "90") (name "unconnected-(CON1-SOUND-Pad1)") (class "Default")
      (node (ref "CON1") (pin "1") (pinfunction "SOUND_1") (pintype "bidirectional"))
    )
    (net (code "91") (name "unconnected-(CON1-{slash}BUSACK-Pad38)") (class "Default")
      (node (ref "CON1") (pin "38") (pinfunction "/BUSACK_38") (pintype "bidirectional"))
    )
    (net (code "92") (name "unconnected-(CON1-{slash}BUSRQ-Pad37)") (class "Default")
      (node (ref "CON1") (pin "37") (pinfunction "/BUSRQ_37") (pintype "bidirectional"))
    )
    (net (code "93") (name "unconnected-(CON1-{slash}EXP-Pad48)") (class "Default")
      (node (ref "CON1") (pin "48") (pinfunction "/EXP_48") (pintype "bidirectional"))
    )
    (net (code "94") (name "unconnected-(CON1-{slash}HALT-Pad34)") (class "Default")
      (node (ref "CON1") (pin "34") (pinfunction "/HALT_34") (pintype "bidirectional"))
    )
    (net (code "95") (name "unconnected-(CON1-{slash}INT-Pad35)") (class "Default")
      (node (ref "CON1") (pin "35") (pinfunction "/INT_35") (pintype "bidirectional"))
    )
    (net (code "96") (name "unconnected-(CON1-{slash}M1-Pad29)") (class "Default")
      (node (ref "CON1") (pin "29") (pinfunction "/M1_29") (pintype "bidirectional"))
    )
    (net (code "97") (name "unconnected-(CON1-{slash}MREQ-Pad28)") (class "Default")
      (node (ref "CON1") (pin "28") (pinfunction "/MREQ_28") (pintype "bidirectional"))
    )
    (net (code "98") (name "unconnected-(CON1-{slash}NMI-Pad36)") (class "Default")
      (node (ref "CON1") (pin "36") (pinfunction "/NMI_36") (pintype "bidirectional"))
    )
    (net (code "99") (name "unconnected-(CON1-{slash}RAMRD-Pad44)") (class "Default")
      (node (ref "CON1") (pin "44") (pinfunction "/RAMRD_44") (pintype "bidirectional"))
    )
    (net (code "100") (name "unconnected-(CON1-{slash}RFSH-Pad30)") (class "Default")
      (node (ref "CON1") (pin "30") (pinfunction "/RFSH_30") (pintype "bidirectional"))
    )
    (net (code "101") (name "unconnected-(CON1-{slash}ROMEN-Pad42)") (class "Default")
      (node (ref "CON1") (pin "42") (pinfunction "/ROMEN_42") (pintype "bidirectional"))
    )
    (net (code "102") (name "unconnected-(CON1-{slash}WAIT-Pad39)") (class "Default")
      (node (ref "CON1") (pin "39") (pinfunction "/WAIT_39") (pintype "bidirectional"))
    )
    (net (code "103") (name "unconnected-(IC1-OSC2-Pad15)") (class "Default")
      (node (ref "IC1") (pin "15") (pinfunction "OSC2_15") (pintype "output"))
    )
    (net (code "104") (name "unconnected-(IC1-RA3-Pad2)") (class "Default")
      (node (ref "IC1") (pin "2") (pinfunction "RA3_2") (pintype "bidirectional"))
    )
    (net (code "105") (name "unconnected-(IC1-T0CKI{slash}RA4-Pad3)") (class "Default")
      (node (ref "IC1") (pin "3") (pinfunction "T0CKI/RA4_3") (pintype "bidirectional"))
    )
    (net (code "106") (name "unconnected-(IC5A-SQW-Pad23)") (class "Default")
      (node (ref "IC5") (pin "23") (pinfunction "SQW_23") (pintype "output"))
    )
    (net (code "107") (name "unconnected-(IC5A-{slash}IRQ-Pad19)") (class "Default")
      (node (ref "IC5") (pin "19") (pinfunction "/IRQ_19") (pintype "output"))
    )
    (net (code "108") (name "unconnected-(IC5A-{slash}RCLR-Pad21)") (class "Default")
      (node (ref "IC5") (pin "21") (pinfunction "/RCLR_21") (pintype "input"))
    )
    (net (code "109") (name "unconnected-(W5100S-MODULE-{slash}INT-Pad11)") (class "Default")
      (node (ref "W5100S-MODULE") (pin "11") (pinfunction "/INT_11") (pintype "output"))
    )
  )
)
